# PCB.net
KiCad netlist of a schematic drawn in EAGLE
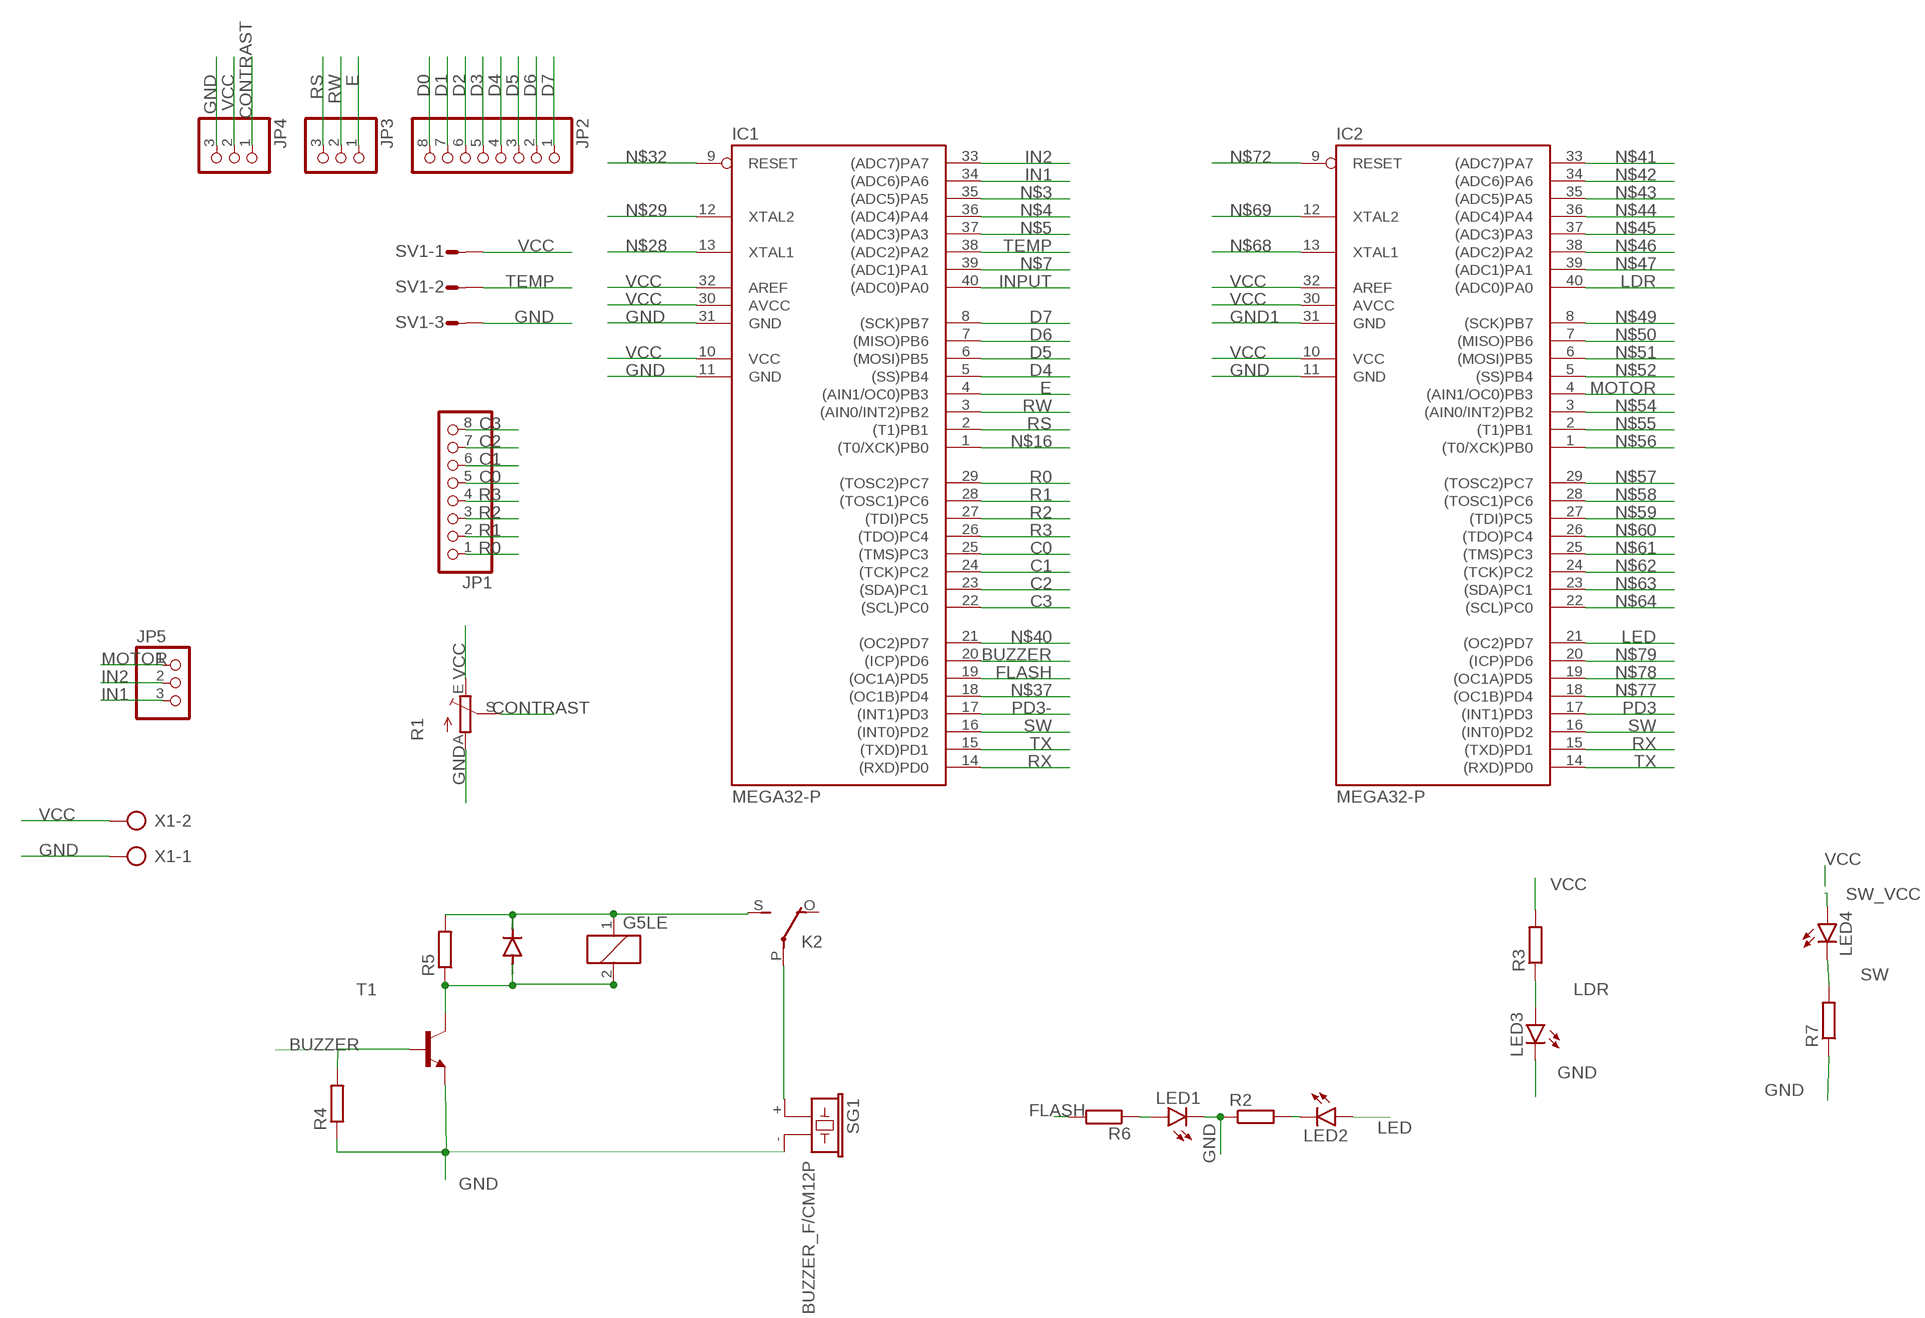
[diagram p0: schematic, sheet 1]

(export (version "E")
  (design (tool "Eeschema 10.0.6"))
  (components
    (comp (ref "D1")
      (value "1N4004")
      (footprint "eagle-import:DO41-10")
      (libsource (lib "eagle-import") (part "1N4004"))
    )
    (comp (ref "IC1")
      (value "MEGA32-P")
      (footprint "eagle-import:DIL40")
      (fields (field (name "MPN") "ATMEGA32-16PU"))
      (libsource (lib "eagle-import") (part "MEGA32-P"))
    )
    (comp (ref "IC2")
      (value "MEGA32-P")
      (footprint "eagle-import:DIL40")
      (fields (field (name "MPN") "ATMEGA32-16PU"))
      (libsource (lib "eagle-import") (part "MEGA32-P"))
    )
    (comp (ref "JP1")
      (value "PINHD-1X8")
      (footprint "eagle-import:1X08")
      (libsource (lib "eagle-import") (part "PINHD-1X8"))
    )
    (comp (ref "JP2")
      (value "PINHD-1X8")
      (footprint "eagle-import:1X08")
      (libsource (lib "eagle-import") (part "PINHD-1X8"))
    )
    (comp (ref "JP3")
      (value "PINHD-1X3")
      (footprint "eagle-import:1X03")
      (libsource (lib "eagle-import") (part "PINHD-1X3"))
    )
    (comp (ref "JP4")
      (value "PINHD-1X3")
      (footprint "eagle-import:1X03")
      (libsource (lib "eagle-import") (part "PINHD-1X3"))
    )
    (comp (ref "JP5")
      (value "PINHD-1X3")
      (footprint "eagle-import:1X03")
      (libsource (lib "eagle-import") (part "PINHD-1X3"))
    )
    (comp (ref "K2")
      (value "G5LE")
      (footprint "eagle-import:G5LE")
      (libsource (lib "eagle-import") (part "G5LE"))
    )
    (comp (ref "LED1")
      (value "LED3MM")
      (footprint "eagle-import:LED3MM")
      (libsource (lib "eagle-import") (part "LED3MM"))
    )
    (comp (ref "LED2")
      (value "LED3MM")
      (footprint "eagle-import:LED3MM")
      (libsource (lib "eagle-import") (part "LED3MM"))
    )
    (comp (ref "LED3")
      (value "LED5MM")
      (footprint "eagle-import:LED5MM")
      (libsource (lib "eagle-import") (part "LED5MM"))
    )
    (comp (ref "LED4")
      (value "LED5MM")
      (footprint "eagle-import:LED5MM")
      (libsource (lib "eagle-import") (part "LED5MM"))
    )
    (comp (ref "R1")
      (value "TRIM_EU-RJ9W")
      (footprint "eagle-import:RJ9W")
      (libsource (lib "eagle-import") (part "TRIM_EU-RJ9W"))
    )
    (comp (ref "R2")
      (value "R-EU_0204/7")
      (footprint "eagle-import:0204_7")
      (libsource (lib "eagle-import") (part "R-EU_0204/7"))
    )
    (comp (ref "R3")
      (value "R-EU_0204/7")
      (footprint "eagle-import:0204_7")
      (libsource (lib "eagle-import") (part "R-EU_0204/7"))
    )
    (comp (ref "R4")
      (value "R-EU_0204/7")
      (footprint "eagle-import:0204_7")
      (libsource (lib "eagle-import") (part "R-EU_0204/7"))
    )
    (comp (ref "R5")
      (value "R-EU_0204/7")
      (footprint "eagle-import:0204_7")
      (libsource (lib "eagle-import") (part "R-EU_0204/7"))
    )
    (comp (ref "R6")
      (value "R-EU_0204/7")
      (footprint "eagle-import:0204_7")
      (libsource (lib "eagle-import") (part "R-EU_0204/7"))
    )
    (comp (ref "R7")
      (value "R-EU_0204/7")
      (footprint "eagle-import:0204_7")
      (libsource (lib "eagle-import") (part "R-EU_0204/7"))
    )
    (comp (ref "SG1")
      (value "BUZZER_F/CM12P")
      (footprint "eagle-import:BUZZER_F_CM12P")
      (libsource (lib "eagle-import") (part "BUZZER_F/CM12P"))
    )
    (comp (ref "SV1")
      (value "CON-AMP-MT_S03P")
      (footprint "eagle-import:CON-AMP-MT_S03P")
      (libsource (lib "eagle-import") (part "CON-AMP-MT_S03P"))
    )
    (comp (ref "T1")
      (value "2N2222-NPN-TO92-EBC")
      (footprint "eagle-import:TO92-EBC")
      (libsource (lib "eagle-import") (part "-NPN-TO92-EBC2N2222"))
    )
    (comp (ref "X1")
      (value "CON-PTR500_AK300/2")
      (footprint "eagle-import:CON-PTR500_AK300_2")
      (libsource (lib "eagle-import") (part "CON-PTR500_AK300/2"))
    )
  )
  (nets
    (net (code "1") (name "/BUZZER") (class "Default")
      (node (ref "IC1") (pin "20") (pinfunction "(ICP)PD6_20") (pintype "bidirectional"))
    )
    (net (code "2") (name "/C0") (class "Default")
      (node (ref "IC1") (pin "25") (pinfunction "(TMS)PC3_25") (pintype "bidirectional"))
      (node (ref "JP1") (pin "5") (pinfunction "5_5") (pintype "passive"))
    )
    (net (code "3") (name "/C1") (class "Default")
      (node (ref "IC1") (pin "24") (pinfunction "(TCK)PC2_24") (pintype "bidirectional"))
      (node (ref "JP1") (pin "6") (pinfunction "6_6") (pintype "passive"))
    )
    (net (code "4") (name "/C2") (class "Default")
      (node (ref "IC1") (pin "23") (pinfunction "(SDA)PC1_23") (pintype "bidirectional"))
      (node (ref "JP1") (pin "7") (pinfunction "7_7") (pintype "passive"))
    )
    (net (code "5") (name "/C3") (class "Default")
      (node (ref "IC1") (pin "22") (pinfunction "(SCL)PC0_22") (pintype "bidirectional"))
      (node (ref "JP1") (pin "8") (pinfunction "8_8") (pintype "passive"))
    )
    (net (code "6") (name "/CONTRAST") (class "Default")
      (node (ref "JP4") (pin "1") (pinfunction "1_1") (pintype "passive"))
      (node (ref "R1") (pin "S") (pinfunction "S_S") (pintype "passive"))
    )
    (net (code "7") (name "/D0") (class "Default")
      (node (ref "JP2") (pin "8") (pinfunction "8_8") (pintype "passive"))
    )
    (net (code "8") (name "/D1") (class "Default")
      (node (ref "JP2") (pin "7") (pinfunction "7_7") (pintype "passive"))
    )
    (net (code "9") (name "/D2") (class "Default")
      (node (ref "JP2") (pin "6") (pinfunction "6_6") (pintype "passive"))
    )
    (net (code "10") (name "/D3") (class "Default")
      (node (ref "JP2") (pin "5") (pinfunction "5_5") (pintype "passive"))
    )
    (net (code "11") (name "/D4") (class "Default")
      (node (ref "IC1") (pin "5") (pinfunction "(SS)PB4_5") (pintype "bidirectional"))
      (node (ref "JP2") (pin "4") (pinfunction "4_4") (pintype "passive"))
    )
    (net (code "12") (name "/D5") (class "Default")
      (node (ref "IC1") (pin "6") (pinfunction "(MOSI)PB5_6") (pintype "bidirectional"))
      (node (ref "JP2") (pin "3") (pinfunction "3_3") (pintype "passive"))
    )
    (net (code "13") (name "/D6") (class "Default")
      (node (ref "IC1") (pin "7") (pinfunction "(MISO)PB6_7") (pintype "bidirectional"))
      (node (ref "JP2") (pin "2") (pinfunction "2_2") (pintype "passive"))
    )
    (net (code "14") (name "/D7") (class "Default")
      (node (ref "IC1") (pin "8") (pinfunction "(SCK)PB7_8") (pintype "bidirectional"))
      (node (ref "JP2") (pin "1") (pinfunction "1_1") (pintype "passive"))
    )
    (net (code "15") (name "/E") (class "Default")
      (node (ref "IC1") (pin "4") (pinfunction "(AIN1/OC0)PB3_4") (pintype "bidirectional"))
      (node (ref "JP3") (pin "1") (pinfunction "1_1") (pintype "passive"))
    )
    (net (code "16") (name "/FLASH") (class "Default")
      (node (ref "IC1") (pin "19") (pinfunction "(OC1A)PD5_19") (pintype "bidirectional"))
      (node (ref "R6") (pin "2") (pinfunction "2_2") (pintype "passive"))
    )
    (net (code "17") (name "/GND") (class "Default")
      (node (ref "IC1") (pin "11") (pinfunction "GND_11") (pintype "power_in"))
      (node (ref "IC1") (pin "31") (pinfunction "GND_31") (pintype "power_in"))
      (node (ref "IC2") (pin "11") (pinfunction "GND_11") (pintype "power_in"))
      (node (ref "JP4") (pin "3") (pinfunction "3_3") (pintype "passive"))
      (node (ref "LED1") (pin "K") (pinfunction "C_K") (pintype "passive"))
      (node (ref "LED3") (pin "K") (pinfunction "C_K") (pintype "passive"))
      (node (ref "R1") (pin "A") (pinfunction "A_A") (pintype "passive"))
      (node (ref "R2") (pin "1") (pinfunction "1_1") (pintype "passive"))
      (node (ref "R4") (pin "1") (pinfunction "1_1") (pintype "passive"))
      (node (ref "R7") (pin "1") (pinfunction "1_1") (pintype "passive"))
      (node (ref "SG1") (pin "-") (pinfunction "2_-") (pintype "passive"))
      (node (ref "SV1") (pin "3") (pinfunction "S_3") (pintype "passive"))
      (node (ref "T1") (pin "E") (pinfunction "E_E") (pintype "passive"))
      (node (ref "X1") (pin "1") (pinfunction "KL_1") (pintype "passive"))
    )
    (net (code "18") (name "/GND1") (class "Default")
      (node (ref "IC2") (pin "31") (pinfunction "GND_31") (pintype "power_in"))
    )
    (net (code "19") (name "/IN1") (class "Default")
      (node (ref "IC1") (pin "34") (pinfunction "(ADC6)PA6_34") (pintype "bidirectional"))
      (node (ref "JP5") (pin "3") (pinfunction "3_3") (pintype "passive"))
    )
    (net (code "20") (name "/IN2") (class "Default")
      (node (ref "IC1") (pin "33") (pinfunction "(ADC7)PA7_33") (pintype "bidirectional"))
      (node (ref "JP5") (pin "2") (pinfunction "2_2") (pintype "passive"))
    )
    (net (code "21") (name "/INPUT") (class "Default")
      (node (ref "IC1") (pin "40") (pinfunction "(ADC0)PA0_40") (pintype "bidirectional"))
    )
    (net (code "22") (name "/LDR") (class "Default")
      (node (ref "IC2") (pin "40") (pinfunction "(ADC0)PA0_40") (pintype "bidirectional"))
      (node (ref "LED3") (pin "A") (pinfunction "A_A") (pintype "passive"))
      (node (ref "R3") (pin "1") (pinfunction "1_1") (pintype "passive"))
    )
    (net (code "23") (name "/LED") (class "Default")
      (node (ref "IC2") (pin "21") (pinfunction "(OC2)PD7_21") (pintype "bidirectional"))
      (node (ref "LED2") (pin "A") (pinfunction "A_A") (pintype "passive"))
    )
    (net (code "24") (name "/MOTOR") (class "Default")
      (node (ref "IC2") (pin "4") (pinfunction "(AIN1/OC0)PB3_4") (pintype "bidirectional"))
      (node (ref "JP5") (pin "1") (pinfunction "1_1") (pintype "passive"))
    )
    (net (code "25") (name "/N$3") (class "Default")
      (node (ref "IC1") (pin "35") (pinfunction "(ADC5)PA5_35") (pintype "bidirectional"))
    )
    (net (code "26") (name "/N$4") (class "Default")
      (node (ref "IC1") (pin "36") (pinfunction "(ADC4)PA4_36") (pintype "bidirectional"))
    )
    (net (code "27") (name "/N$5") (class "Default")
      (node (ref "IC1") (pin "37") (pinfunction "(ADC3)PA3_37") (pintype "bidirectional"))
    )
    (net (code "28") (name "/N$7") (class "Default")
      (node (ref "IC1") (pin "39") (pinfunction "(ADC1)PA1_39") (pintype "bidirectional"))
    )
    (net (code "29") (name "/N$16") (class "Default")
      (node (ref "IC1") (pin "1") (pinfunction "(T0/XCK)PB0_1") (pintype "bidirectional"))
    )
    (net (code "30") (name "/N$28") (class "Default")
      (node (ref "IC1") (pin "13") (pinfunction "XTAL1_13") (pintype "bidirectional"))
    )
    (net (code "31") (name "/N$29") (class "Default")
      (node (ref "IC1") (pin "12") (pinfunction "XTAL2_12") (pintype "bidirectional"))
    )
    (net (code "32") (name "/N$32") (class "Default")
      (node (ref "IC1") (pin "9") (pinfunction "RESET_9") (pintype "input"))
    )
    (net (code "33") (name "/N$37") (class "Default")
      (node (ref "IC1") (pin "18") (pinfunction "(OC1B)PD4_18") (pintype "bidirectional"))
    )
    (net (code "34") (name "/N$40") (class "Default")
      (node (ref "IC1") (pin "21") (pinfunction "(OC2)PD7_21") (pintype "bidirectional"))
    )
    (net (code "35") (name "/N$41") (class "Default")
      (node (ref "IC2") (pin "33") (pinfunction "(ADC7)PA7_33") (pintype "bidirectional"))
    )
    (net (code "36") (name "/N$42") (class "Default")
      (node (ref "IC2") (pin "34") (pinfunction "(ADC6)PA6_34") (pintype "bidirectional"))
    )
    (net (code "37") (name "/N$43") (class "Default")
      (node (ref "IC2") (pin "35") (pinfunction "(ADC5)PA5_35") (pintype "bidirectional"))
    )
    (net (code "38") (name "/N$44") (class "Default")
      (node (ref "IC2") (pin "36") (pinfunction "(ADC4)PA4_36") (pintype "bidirectional"))
    )
    (net (code "39") (name "/N$45") (class "Default")
      (node (ref "IC2") (pin "37") (pinfunction "(ADC3)PA3_37") (pintype "bidirectional"))
    )
    (net (code "40") (name "/N$46") (class "Default")
      (node (ref "IC2") (pin "38") (pinfunction "(ADC2)PA2_38") (pintype "bidirectional"))
    )
    (net (code "41") (name "/N$47") (class "Default")
      (node (ref "IC2") (pin "39") (pinfunction "(ADC1)PA1_39") (pintype "bidirectional"))
    )
    (net (code "42") (name "/N$49") (class "Default")
      (node (ref "IC2") (pin "8") (pinfunction "(SCK)PB7_8") (pintype "bidirectional"))
    )
    (net (code "43") (name "/N$50") (class "Default")
      (node (ref "IC2") (pin "7") (pinfunction "(MISO)PB6_7") (pintype "bidirectional"))
    )
    (net (code "44") (name "/N$51") (class "Default")
      (node (ref "IC2") (pin "6") (pinfunction "(MOSI)PB5_6") (pintype "bidirectional"))
    )
    (net (code "45") (name "/N$52") (class "Default")
      (node (ref "IC2") (pin "5") (pinfunction "(SS)PB4_5") (pintype "bidirectional"))
    )
    (net (code "46") (name "/N$54") (class "Default")
      (node (ref "IC2") (pin "3") (pinfunction "(AIN0/INT2)PB2_3") (pintype "bidirectional"))
    )
    (net (code "47") (name "/N$55") (class "Default")
      (node (ref "IC2") (pin "2") (pinfunction "(T1)PB1_2") (pintype "bidirectional"))
    )
    (net (code "48") (name "/N$56") (class "Default")
      (node (ref "IC2") (pin "1") (pinfunction "(T0/XCK)PB0_1") (pintype "bidirectional"))
    )
    (net (code "49") (name "/N$57") (class "Default")
      (node (ref "IC2") (pin "29") (pinfunction "(TOSC2)PC7_29") (pintype "bidirectional"))
    )
    (net (code "50") (name "/N$58") (class "Default")
      (node (ref "IC2") (pin "28") (pinfunction "(TOSC1)PC6_28") (pintype "bidirectional"))
    )
    (net (code "51") (name "/N$59") (class "Default")
      (node (ref "IC2") (pin "27") (pinfunction "(TDI)PC5_27") (pintype "bidirectional"))
    )
    (net (code "52") (name "/N$60") (class "Default")
      (node (ref "IC2") (pin "26") (pinfunction "(TDO)PC4_26") (pintype "bidirectional"))
    )
    (net (code "53") (name "/N$61") (class "Default")
      (node (ref "IC2") (pin "25") (pinfunction "(TMS)PC3_25") (pintype "bidirectional"))
    )
    (net (code "54") (name "/N$62") (class "Default")
      (node (ref "IC2") (pin "24") (pinfunction "(TCK)PC2_24") (pintype "bidirectional"))
    )
    (net (code "55") (name "/N$63") (class "Default")
      (node (ref "IC2") (pin "23") (pinfunction "(SDA)PC1_23") (pintype "bidirectional"))
    )
    (net (code "56") (name "/N$64") (class "Default")
      (node (ref "IC2") (pin "22") (pinfunction "(SCL)PC0_22") (pintype "bidirectional"))
    )
    (net (code "57") (name "/N$68") (class "Default")
      (node (ref "IC2") (pin "13") (pinfunction "XTAL1_13") (pintype "bidirectional"))
    )
    (net (code "58") (name "/N$69") (class "Default")
      (node (ref "IC2") (pin "12") (pinfunction "XTAL2_12") (pintype "bidirectional"))
    )
    (net (code "59") (name "/N$72") (class "Default")
      (node (ref "IC2") (pin "9") (pinfunction "RESET_9") (pintype "input"))
    )
    (net (code "60") (name "/N$77") (class "Default")
      (node (ref "IC2") (pin "18") (pinfunction "(OC1B)PD4_18") (pintype "bidirectional"))
    )
    (net (code "61") (name "/N$78") (class "Default")
      (node (ref "IC2") (pin "19") (pinfunction "(OC1A)PD5_19") (pintype "bidirectional"))
    )
    (net (code "62") (name "/N$79") (class "Default")
      (node (ref "IC2") (pin "20") (pinfunction "(ICP)PD6_20") (pintype "bidirectional"))
    )
    (net (code "63") (name "/PD3") (class "Default")
      (node (ref "IC2") (pin "17") (pinfunction "(INT1)PD3_17") (pintype "bidirectional"))
    )
    (net (code "64") (name "/PD3-") (class "Default")
      (node (ref "IC1") (pin "17") (pinfunction "(INT1)PD3_17") (pintype "bidirectional"))
    )
    (net (code "65") (name "/R0") (class "Default")
      (node (ref "IC1") (pin "29") (pinfunction "(TOSC2)PC7_29") (pintype "bidirectional"))
      (node (ref "JP1") (pin "1") (pinfunction "1_1") (pintype "passive"))
    )
    (net (code "66") (name "/R1") (class "Default")
      (node (ref "IC1") (pin "28") (pinfunction "(TOSC1)PC6_28") (pintype "bidirectional"))
      (node (ref "JP1") (pin "2") (pinfunction "2_2") (pintype "passive"))
    )
    (net (code "67") (name "/R2") (class "Default")
      (node (ref "IC1") (pin "27") (pinfunction "(TDI)PC5_27") (pintype "bidirectional"))
      (node (ref "JP1") (pin "3") (pinfunction "3_3") (pintype "passive"))
    )
    (net (code "68") (name "/R3") (class "Default")
      (node (ref "IC1") (pin "26") (pinfunction "(TDO)PC4_26") (pintype "bidirectional"))
      (node (ref "JP1") (pin "4") (pinfunction "4_4") (pintype "passive"))
    )
    (net (code "69") (name "/RS") (class "Default")
      (node (ref "IC1") (pin "2") (pinfunction "(T1)PB1_2") (pintype "bidirectional"))
      (node (ref "JP3") (pin "3") (pinfunction "3_3") (pintype "passive"))
    )
    (net (code "70") (name "/RW") (class "Default")
      (node (ref "IC1") (pin "3") (pinfunction "(AIN0/INT2)PB2_3") (pintype "bidirectional"))
      (node (ref "JP3") (pin "2") (pinfunction "2_2") (pintype "passive"))
    )
    (net (code "71") (name "/RX") (class "Default")
      (node (ref "IC1") (pin "14") (pinfunction "(RXD)PD0_14") (pintype "bidirectional"))
      (node (ref "IC2") (pin "15") (pinfunction "(TXD)PD1_15") (pintype "bidirectional"))
    )
    (net (code "72") (name "/SW") (class "Default")
      (node (ref "IC1") (pin "16") (pinfunction "(INT0)PD2_16") (pintype "bidirectional"))
      (node (ref "IC2") (pin "16") (pinfunction "(INT0)PD2_16") (pintype "bidirectional"))
      (node (ref "LED4") (pin "K") (pinfunction "C_K") (pintype "passive"))
      (node (ref "R7") (pin "2") (pinfunction "2_2") (pintype "passive"))
    )
    (net (code "73") (name "/SW_VCC") (class "Default")
      (node (ref "LED4") (pin "A") (pinfunction "A_A") (pintype "passive"))
    )
    (net (code "74") (name "/TEMP") (class "Default")
      (node (ref "IC1") (pin "38") (pinfunction "(ADC2)PA2_38") (pintype "bidirectional"))
      (node (ref "SV1") (pin "2") (pinfunction "S_2") (pintype "passive"))
    )
    (net (code "75") (name "/TX") (class "Default")
      (node (ref "IC1") (pin "15") (pinfunction "(TXD)PD1_15") (pintype "bidirectional"))
      (node (ref "IC2") (pin "14") (pinfunction "(RXD)PD0_14") (pintype "bidirectional"))
    )
    (net (code "76") (name "/VCC") (class "Default")
      (node (ref "IC1") (pin "10") (pinfunction "VCC_10") (pintype "power_in"))
      (node (ref "IC1") (pin "30") (pinfunction "AVCC_30") (pintype "power_in"))
      (node (ref "IC1") (pin "32") (pinfunction "AREF_32") (pintype "passive"))
      (node (ref "IC2") (pin "10") (pinfunction "VCC_10") (pintype "power_in"))
      (node (ref "IC2") (pin "30") (pinfunction "AVCC_30") (pintype "power_in"))
      (node (ref "IC2") (pin "32") (pinfunction "AREF_32") (pintype "passive"))
      (node (ref "JP4") (pin "2") (pinfunction "2_2") (pintype "passive"))
      (node (ref "R1") (pin "E") (pinfunction "E_E") (pintype "passive"))
      (node (ref "R3") (pin "2") (pinfunction "2_2") (pintype "passive"))
      (node (ref "SV1") (pin "1") (pinfunction "S_1") (pintype "passive"))
      (node (ref "X1") (pin "2") (pinfunction "KL_2") (pintype "passive"))
    )
    (net (code "77") (name "Net-(D1-PadA)") (class "Default")
      (node (ref "D1") (pin "A") (pinfunction "A_A") (pintype "passive"))
      (node (ref "K2") (pin "2") (pinfunction "2_2") (pintype "passive"))
      (node (ref "R5") (pin "1") (pinfunction "1_1") (pintype "passive"))
      (node (ref "T1") (pin "C") (pinfunction "C_C") (pintype "passive"))
    )
    (net (code "78") (name "Net-(D1-PadC)") (class "Default")
      (node (ref "D1") (pin "C") (pinfunction "C_C") (pintype "passive"))
      (node (ref "K2") (pin "1") (pinfunction "1_1") (pintype "passive"))
      (node (ref "K2") (pin "S") (pinfunction "S_S") (pintype "passive"))
      (node (ref "R5") (pin "2") (pinfunction "2_2") (pintype "passive"))
    )
    (net (code "79") (name "Net-(LED1-PadA)") (class "Default")
      (node (ref "LED1") (pin "A") (pinfunction "A_A") (pintype "passive"))
      (node (ref "R6") (pin "1") (pinfunction "1_1") (pintype "passive"))
    )
    (net (code "80") (name "Net-(LED2-C)") (class "Default")
      (node (ref "LED2") (pin "K") (pinfunction "C_K") (pintype "passive"))
      (node (ref "R2") (pin "2") (pinfunction "2_2") (pintype "passive"))
    )
    (net (code "81") (name "Net-(R4-Pad2)") (class "Default")
      (node (ref "R4") (pin "2") (pinfunction "2_2") (pintype "passive"))
      (node (ref "T1") (pin "B") (pinfunction "B_B") (pintype "passive"))
    )
    (net (code "82") (name "Net-(SG1-1)") (class "Default")
      (node (ref "K2") (pin "P") (pinfunction "P_P") (pintype "passive"))
      (node (ref "SG1") (pin "+") (pinfunction "1_+") (pintype "passive"))
    )
    (net (code "83") (name "unconnected-(K2-PadO)") (class "Default")
      (node (ref "K2") (pin "O") (pinfunction "O_O") (pintype "passive"))
    )
  )
)
